# nano_3.net
KiCad netlist of a schematic drawn in EAGLE
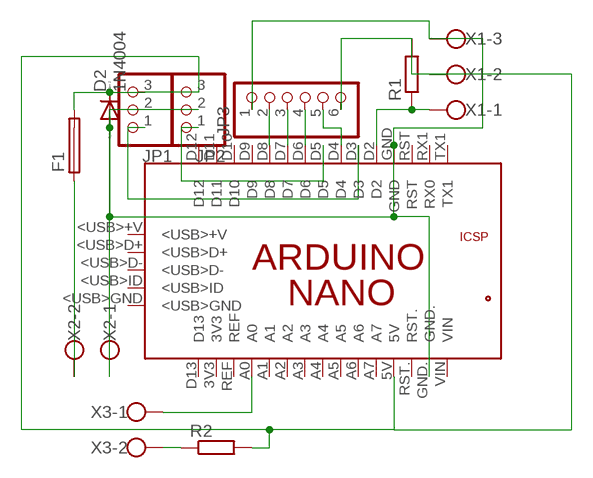
[diagram p0: schematic, sheet 1]

(export (version "E")
  (design (tool "Eeschema 10.0.6"))
  (components
    (comp (ref "D2")
      (value "1N4004")
      (footprint "eagle-import:DO41-10")
      (libsource (lib "eagle-import") (part "1N4004"))
    )
    (comp (ref "F1")
      (value "GSH15")
      (footprint "eagle-import:GSH15")
      (fields (field (name "MPN") "64900001039"))
      (libsource (lib "eagle-import") (part "GSH15"))
    )
    (comp (ref "JP1")
      (value "PINHD-1X3")
      (footprint "eagle-import:1X03")
      (libsource (lib "eagle-import") (part "PINHD-1X3"))
    )
    (comp (ref "JP2")
      (value "PINHD-1X3")
      (footprint "eagle-import:1X03")
      (libsource (lib "eagle-import") (part "PINHD-1X3"))
    )
    (comp (ref "JP3")
      (value "PINHD-1X6")
      (footprint "eagle-import:1X06")
      (libsource (lib "eagle-import") (part "PINHD-1X6"))
    )
    (comp (ref "PCB2")
      (value "ARDUINO_NANO")
      (footprint "eagle-import:ARDUINO_NANO")
      (libsource (lib "eagle-import") (part "ARDUINO_NANO"))
    )
    (comp (ref "R1")
      (value "R-EU_0207/15")
      (footprint "eagle-import:0207_15")
      (libsource (lib "eagle-import") (part "R-EU_0207/15"))
    )
    (comp (ref "R2")
      (value "R-EU_0204/7")
      (footprint "eagle-import:0204_7")
      (libsource (lib "eagle-import") (part "R-EU_0204/7"))
    )
    (comp (ref "X1")
      (value "W237-103")
      (footprint "eagle-import:W237-103")
      (fields (field (name "MPN") "237-103"))
      (libsource (lib "eagle-import") (part "W237-103"))
    )
    (comp (ref "X2")
      (value "W237-102")
      (footprint "eagle-import:W237-102")
      (fields (field (name "MPN") "237-102"))
      (libsource (lib "eagle-import") (part "W237-102"))
    )
    (comp (ref "X3")
      (value "W237-102")
      (footprint "eagle-import:W237-102")
      (fields (field (name "MPN") "237-102"))
      (libsource (lib "eagle-import") (part "W237-102"))
    )
  )
  (nets
    (net (code "1") (name "Net-(JP1-Pad1)") (class "Default")
      (node (ref "JP1") (pin "1") (pinfunction "1_1") (pintype "passive"))
      (node (ref "PCB2") (pin "D3") (pinfunction "D3_D3") (pintype "bidirectional"))
    )
    (net (code "2") (name "Net-(JP2-Pad1)") (class "Default")
      (node (ref "JP2") (pin "1") (pinfunction "1_1") (pintype "passive"))
      (node (ref "PCB2") (pin "D5") (pinfunction "D5_D5") (pintype "bidirectional"))
    )
    (net (code "3") (name "Net-(JP3-Pad2)") (class "Default")
      (node (ref "JP3") (pin "2") (pinfunction "2_2") (pintype "passive"))
      (node (ref "PCB2") (pin "D8") (pinfunction "D8_D8") (pintype "bidirectional"))
    )
    (net (code "4") (name "Net-(JP3-Pad3)") (class "Default")
      (node (ref "JP3") (pin "3") (pinfunction "3_3") (pintype "passive"))
      (node (ref "PCB2") (pin "D7") (pinfunction "D7_D7") (pintype "bidirectional"))
    )
    (net (code "5") (name "Net-(JP3-Pad4)") (class "Default")
      (node (ref "JP3") (pin "4") (pinfunction "4_4") (pintype "passive"))
      (node (ref "PCB2") (pin "D6") (pinfunction "D6_D6") (pintype "bidirectional"))
    )
    (net (code "6") (name "Net-(JP3-Pad5)") (class "Default")
      (node (ref "JP3") (pin "5") (pinfunction "5_5") (pintype "passive"))
      (node (ref "PCB2") (pin "D4") (pinfunction "D4_D4") (pintype "bidirectional"))
    )
    (net (code "7") (name "Net-(X1A-KL)") (class "Default")
      (node (ref "PCB2") (pin "D2") (pinfunction "D2_D2") (pintype "bidirectional"))
      (node (ref "R1") (pin "1") (pinfunction "1_1") (pintype "passive"))
      (node (ref "X1") (pin "1") (pinfunction "KL_1") (pintype "passive"))
    )
    (net (code "8") (name "Net-(X1B-KL)") (class "Default")
      (node (ref "D2") (pin "C") (pinfunction "C_C") (pintype "passive"))
      (node (ref "F1") (pin "2") (pinfunction "2_2") (pintype "passive"))
      (node (ref "JP1") (pin "3") (pinfunction "3_3") (pintype "passive"))
      (node (ref "JP2") (pin "3") (pinfunction "3_3") (pintype "passive"))
      (node (ref "JP3") (pin "6") (pinfunction "6_6") (pintype "passive"))
      (node (ref "PCB2") (pin "5V") (pinfunction "5V_5V") (pintype "bidirectional"))
      (node (ref "R1") (pin "2") (pinfunction "2_2") (pintype "passive"))
      (node (ref "R2") (pin "2") (pinfunction "2_2") (pintype "passive"))
      (node (ref "X1") (pin "2") (pinfunction "KL_2") (pintype "passive"))
    )
    (net (code "9") (name "Net-(X1C-KL)") (class "Default")
      (node (ref "D2") (pin "A") (pinfunction "A_A") (pintype "passive"))
      (node (ref "JP1") (pin "2") (pinfunction "2_2") (pintype "passive"))
      (node (ref "JP2") (pin "2") (pinfunction "2_2") (pintype "passive"))
      (node (ref "JP3") (pin "1") (pinfunction "1_1") (pintype "passive"))
      (node (ref "PCB2") (pin "GND") (pinfunction "GND_GND") (pintype "bidirectional"))
      (node (ref "PCB2") (pin "GND.") (pinfunction "GND._GND.") (pintype "bidirectional"))
      (node (ref "X1") (pin "3") (pinfunction "KL_3") (pintype "passive"))
      (node (ref "X2") (pin "1") (pinfunction "KL_1") (pintype "passive"))
    )
    (net (code "10") (name "Net-(X2B-KL)") (class "Default")
      (node (ref "F1") (pin "1") (pinfunction "1_1") (pintype "passive"))
      (node (ref "X2") (pin "2") (pinfunction "KL_2") (pintype "passive"))
    )
    (net (code "11") (name "Net-(X3A-KL)") (class "Default")
      (node (ref "PCB2") (pin "A0") (pinfunction "A0_A0") (pintype "bidirectional"))
      (node (ref "X3") (pin "1") (pinfunction "KL_1") (pintype "passive"))
    )
    (net (code "12") (name "Net-(X3B-KL)") (class "Default")
      (node (ref "R2") (pin "1") (pinfunction "1_1") (pintype "passive"))
      (node (ref "X3") (pin "2") (pinfunction "KL_2") (pintype "passive"))
    )
    (net (code "13") (name "unconnected-(PCB2-Pad3V3)") (class "Default")
      (node (ref "PCB2") (pin "3V3") (pinfunction "3V3_3V3") (pintype "bidirectional"))
    )
    (net (code "14") (name "unconnected-(PCB2-Pad5V.)") (class "Default")
      (node (ref "PCB2") (pin "5V.") (pinfunction "5V._5V.") (pintype "bidirectional"))
    )
    (net (code "15") (name "unconnected-(PCB2-Pad<USB>+V)") (class "Default")
      (node (ref "PCB2") (pin "<USB>+V") (pinfunction "<USB>+V_<USB>+V") (pintype "bidirectional"))
    )
    (net (code "16") (name "unconnected-(PCB2-Pad<USB>D+)") (class "Default")
      (node (ref "PCB2") (pin "<USB>D+") (pinfunction "<USB>D+_<USB>D+") (pintype "bidirectional"))
    )
    (net (code "17") (name "unconnected-(PCB2-Pad<USB>D-)") (class "Default")
      (node (ref "PCB2") (pin "<USB>D-") (pinfunction "<USB>D-_<USB>D-") (pintype "bidirectional"))
    )
    (net (code "18") (name "unconnected-(PCB2-Pad<USB>GND)") (class "Default")
      (node (ref "PCB2") (pin "<USB>GND") (pinfunction "<USB>GND_<USB>GND") (pintype "bidirectional"))
    )
    (net (code "19") (name "unconnected-(PCB2-Pad<USB>ID)") (class "Default")
      (node (ref "PCB2") (pin "<USB>ID") (pinfunction "<USB>ID_<USB>ID") (pintype "bidirectional"))
    )
    (net (code "20") (name "unconnected-(PCB2-PadA1)") (class "Default")
      (node (ref "PCB2") (pin "A1") (pinfunction "A1_A1") (pintype "bidirectional"))
    )
    (net (code "21") (name "unconnected-(PCB2-PadA2)") (class "Default")
      (node (ref "PCB2") (pin "A2") (pinfunction "A2_A2") (pintype "bidirectional"))
    )
    (net (code "22") (name "unconnected-(PCB2-PadA3)") (class "Default")
      (node (ref "PCB2") (pin "A3") (pinfunction "A3_A3") (pintype "bidirectional"))
    )
    (net (code "23") (name "unconnected-(PCB2-PadA4)") (class "Default")
      (node (ref "PCB2") (pin "A4") (pinfunction "A4_A4") (pintype "bidirectional"))
    )
    (net (code "24") (name "unconnected-(PCB2-PadA5)") (class "Default")
      (node (ref "PCB2") (pin "A5") (pinfunction "A5_A5") (pintype "bidirectional"))
    )
    (net (code "25") (name "unconnected-(PCB2-PadA6)") (class "Default")
      (node (ref "PCB2") (pin "A6") (pinfunction "A6_A6") (pintype "bidirectional"))
    )
    (net (code "26") (name "unconnected-(PCB2-PadA7)") (class "Default")
      (node (ref "PCB2") (pin "A7") (pinfunction "A7_A7") (pintype "bidirectional"))
    )
    (net (code "27") (name "unconnected-(PCB2-PadD9)") (class "Default")
      (node (ref "PCB2") (pin "D9") (pinfunction "D9_D9") (pintype "bidirectional"))
    )
    (net (code "28") (name "unconnected-(PCB2-PadD10)") (class "Default")
      (node (ref "PCB2") (pin "D10") (pinfunction "D10_D10") (pintype "bidirectional"))
    )
    (net (code "29") (name "unconnected-(PCB2-PadD11)") (class "Default")
      (node (ref "PCB2") (pin "D11") (pinfunction "D11_D11") (pintype "bidirectional"))
    )
    (net (code "30") (name "unconnected-(PCB2-PadD12)") (class "Default")
      (node (ref "PCB2") (pin "D12") (pinfunction "D12_D12") (pintype "bidirectional"))
    )
    (net (code "31") (name "unconnected-(PCB2-PadD13)") (class "Default")
      (node (ref "PCB2") (pin "D13") (pinfunction "D13_D13") (pintype "bidirectional"))
    )
    (net (code "32") (name "unconnected-(PCB2-PadGND_)") (class "Default")
      (node (ref "PCB2") (pin "GND_") (pinfunction "GND__GND_") (pintype "bidirectional"))
    )
    (net (code "33") (name "unconnected-(PCB2-PadMISO)") (class "Default")
      (node (ref "PCB2") (pin "MISO") (pinfunction "MISO_MISO") (pintype "bidirectional"))
    )
    (net (code "34") (name "unconnected-(PCB2-PadMOSI)") (class "Default")
      (node (ref "PCB2") (pin "MOSI") (pinfunction "MOSI_MOSI") (pintype "bidirectional"))
    )
    (net (code "35") (name "unconnected-(PCB2-PadREF)") (class "Default")
      (node (ref "PCB2") (pin "REF") (pinfunction "REF_REF") (pintype "bidirectional"))
    )
    (net (code "36") (name "unconnected-(PCB2-PadRESET..)") (class "Default")
      (node (ref "PCB2") (pin "RESET..") (pinfunction "RESET.._RESET..") (pintype "bidirectional"))
    )
    (net (code "37") (name "unconnected-(PCB2-PadRST)") (class "Default")
      (node (ref "PCB2") (pin "RST") (pinfunction "RST_RST") (pintype "bidirectional"))
    )
    (net (code "38") (name "unconnected-(PCB2-PadRST.)") (class "Default")
      (node (ref "PCB2") (pin "RST.") (pinfunction "RST._RST.") (pintype "bidirectional"))
    )
    (net (code "39") (name "unconnected-(PCB2-PadSCK)") (class "Default")
      (node (ref "PCB2") (pin "SCK") (pinfunction "SCK_SCK") (pintype "bidirectional"))
    )
    (net (code "40") (name "unconnected-(PCB2-PadTX1)") (class "Default")
      (node (ref "PCB2") (pin "TX1") (pinfunction "TX1_TX1") (pintype "bidirectional"))
    )
    (net (code "41") (name "unconnected-(PCB2-PadVIN)") (class "Default")
      (node (ref "PCB2") (pin "VIN") (pinfunction "VIN_VIN") (pintype "bidirectional"))
    )
    (net (code "42") (name "unconnected-(PCB2-RX0-PadRX1)") (class "Default")
      (node (ref "PCB2") (pin "RX1") (pinfunction "RX0_RX1") (pintype "bidirectional"))
    )
  )
)
